# Protections.net
KiCad netlist of a schematic drawn in Altium Designer
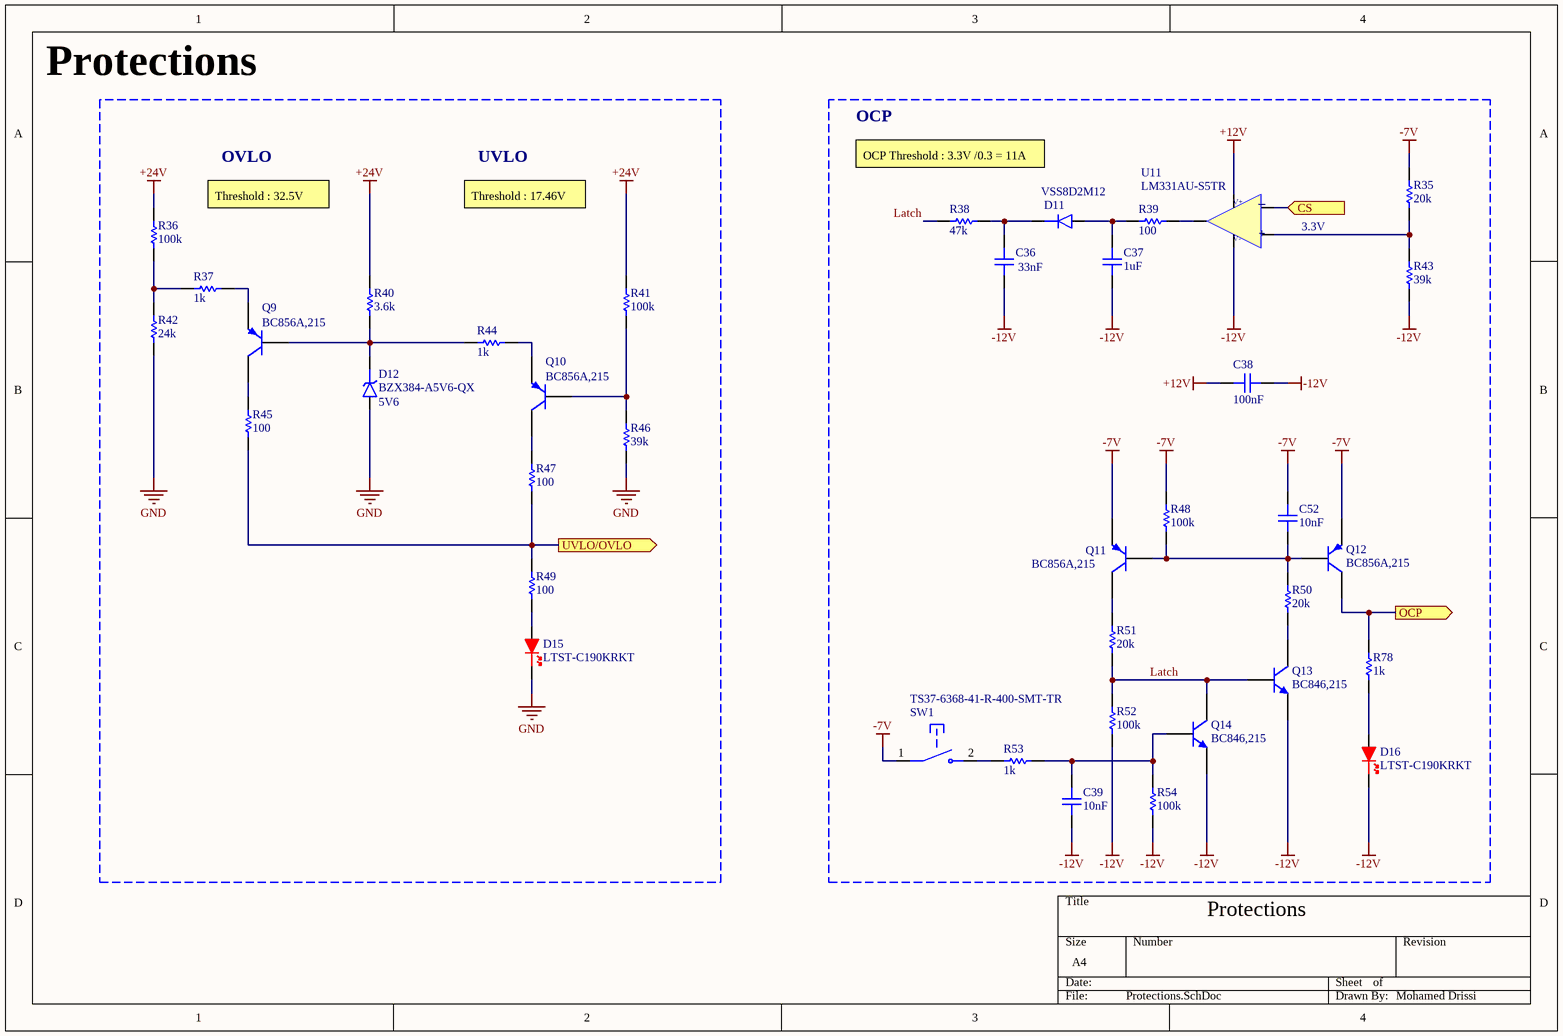
[diagram p0: Protections.SchDoc]

(export (version "E")
  (design (tool "Eeschema 10.0.6"))
  (components
    (comp (ref "C36")
      (value "CC0603KRX7R0BB333")
      (footprint "cap_0603")
      (description "100V 33nF X7R ±10% 0603 Multilayer Ceramic Capacitors MLCC - SMD/SMT ROHS")
      (fields (field (name "MANUFACTURER") "Yageo Group") (field (name "CAPACITANCE") "33nF"))
      (libsource (lib "Inverting buck boost") (part "Yageo CC0603KRX7R0BB333"))
    )
    (comp (ref "C37")
      (value "885382208005")
      (footprint "cap_1206")
      (description "WCAP-CSST 1206 (3216Metric) ceramic capacitor 0.126Lx0.063W 3.20mmx1.60mm X7R ±10% 1muF")
      (fields (field (name "MANUFACTURER") "Wurth Elektronik") (field (name "CAPACITANCE") "1uF"))
      (libsource (lib "Inverting buck boost") (part "Wurth 885382208005"))
    )
    (comp (ref "C38")
      (value "GMC10X7R104K100NT")
      (footprint "cap_0603")
      (description "100V 100nF X7R ±10% 0603 Multilayer Ceramic Capacitors MLCC - SMD/SMT ROHS")
      (fields (field (name "MANUFACTURER") "Cal-Chip Electronics") (field (name "CAPACITANCE") "100nF"))
      (libsource (lib "Inverting buck boost") (part "Cal-chip GMC10X7R104K100NT"))
    )
    (comp (ref "C39")
      (value "C0603C103K4RACTU")
      (footprint "cap_0603")
      (description "Multilayer Ceramic Capacitors MLCC - SMD/SMT 16V 0.01uF X7R 0603 10%")
      (fields
        (field (name "MANUFACTURER") "Yageo Group")
        (field (name "TOLERANCE") "10%")
        (field (name "CAPACITANCE") "10nF")
      )
      (libsource (lib "Inverting buck boost") (part "Yageo C0603C103K4RACTU"))
    )
    (comp (ref "C52")
      (value "C0603C103K4RACTU")
      (footprint "cap_0603")
      (description "Multilayer Ceramic Capacitors MLCC - SMD/SMT 16V 0.01uF X7R 0603 10%")
      (fields
        (field (name "MANUFACTURER") "Yageo Group")
        (field (name "TOLERANCE") "10%")
        (field (name "CAPACITANCE") "10nF")
      )
      (libsource (lib "Inverting buck boost") (part "Yageo C0603C103K4RACTU"))
    )
    (comp (ref "D11")
      (value "VSS8D2M12")
      (footprint "DO-221AD")
      (description "Rectifier Diode, Schottky, 1 Phase, 1 Element, 2A, 120V V(RRM), Silicon, DO-221AD")
      (fields
        (field (name "MANUFACTURER") "Vishay")
        (field (name "MANUFACTURER PART NUMBER") "VSS8D2M12-M3/H")
      )
      (libsource (lib "Inverting buck boost") (part "Vishay VSS8D2M12-M3/H"))
    )
    (comp (ref "D12")
      (value "BZX384-A5V6-QX")
      (footprint "SOD-323")
      (description "Diode Zener 5.6V 300MW SOD323")
      (fields (field (name "MANUFACTURER") "Nexperia") (field (name "ZENER VOLTAGE") "5V6"))
      (libsource (lib "Inverting buck boost") (part "NXP BZX384-A5V6-QX"))
    )
    (comp (ref "D15")
      (value "LTST-C190KRKT")
      (footprint "LED")
      (description "LED red 0603 wavelength 631nm light intensity 18~180mcd Front Mounting")
      (fields (field (name "MANUFACTURER") "Diodes Inc.") (field (name "TOLERANCE") "20%"))
      (libsource (lib "Inverting buck boost") (part "Diodes LTST-C190KRKT"))
    )
    (comp (ref "D16")
      (value "LTST-C190KRKT")
      (footprint "LED")
      (description "LED red 0603 wavelength 631nm light intensity 18~180mcd Front Mounting")
      (fields (field (name "MANUFACTURER") "Diodes Inc.") (field (name "TOLERANCE") "20%"))
      (libsource (lib "Inverting buck boost") (part "Diodes LTST-C190KRKT"))
    )
    (comp (ref "Q9")
      (value "BC856A,215")
      (footprint "sot23")
      (description "BC856 Series 65 V 100 mA SMT PNP General Purpose Transistor - SOT-23")
      (fields (field (name "MANUFACTURER") "Nexperia"))
      (libsource (lib "Inverting buck boost") (part "NXP BC856A,215"))
    )
    (comp (ref "Q10")
      (value "BC856A,215")
      (footprint "sot23")
      (description "BC856 Series 65 V 100 mA SMT PNP General Purpose Transistor - SOT-23")
      (fields (field (name "MANUFACTURER") "Nexperia"))
      (libsource (lib "Inverting buck boost") (part "NXP BC856A,215"))
    )
    (comp (ref "Q11")
      (value "BC856A,215")
      (footprint "sot23")
      (description "BC856 Series 65 V 100 mA SMT PNP General Purpose Transistor - SOT-23")
      (fields (field (name "MANUFACTURER") "Nexperia"))
      (libsource (lib "Inverting buck boost") (part "NXP BC856A,215"))
    )
    (comp (ref "Q12")
      (value "BC856A,215")
      (footprint "sot23")
      (description "BC856 Series 65 V 100 mA SMT PNP General Purpose Transistor - SOT-23")
      (fields (field (name "MANUFACTURER") "Nexperia"))
      (libsource (lib "Inverting buck boost") (part "NXP BC856A,215"))
    )
    (comp (ref "Q13")
      (value "BC846,215")
      (footprint "sot23")
      (description "BC846 Series 65 V 100 mA SMT NPN General Purpose Transistor - SOT-23")
      (fields (field (name "MANUFACTURER") "Nexperia"))
      (libsource (lib "Inverting buck boost") (part "NXP BC846,215"))
    )
    (comp (ref "Q14")
      (value "BC846,215")
      (footprint "sot23")
      (description "BC846 Series 65 V 100 mA SMT NPN General Purpose Transistor - SOT-23")
      (fields (field (name "MANUFACTURER") "Nexperia"))
      (libsource (lib "Inverting buck boost") (part "NXP BC846,215"))
    )
    (comp (ref "R35")
      (value "20k")
      (footprint "res_0603")
      (description "63mW Thin Film Resistor ±50ppm/℃ ±1% 20kΩ 0603 Chip Resistor - Surface Mount ROHS")
      (fields
        (field (name "MANUFACTURER") "TE Connectivity")
        (field (name "MANUFACTURER PART NUMBER") "8-1879337-8")
      )
      (libsource (lib "Inverting buck boost") (part "TE 8-1879337-8"))
    )
    (comp (ref "R36")
      (value "CRCW0603100KFKEA")
      (footprint "res_0603")
      (description "Res Thick Film 0603 100K Ohm 1% 1/3W ±100ppm/°C Molded SMD SMD Paper T/R")
      (fields
        (field (name "MANUFACTURER") "Vishay")
        (field (name "MANUFACTURER PART NUMBER") "CRCW0603100KFKEAHP")
        (field (name "RESISTANCE") "100k")
      )
      (libsource (lib "Inverting buck boost") (part "Vishay CRCW0603100KFKEAHP"))
    )
    (comp (ref "R37")
      (value "RC0603FR-071KL")
      (footprint "res_0603")
      (description "Res Thick Film 0603 1K Ohm 1% 0.1W(1/10W) ±100ppm/°C Pad SMD T/R / RES SMD 1K OHM 1% 1/10W 0603")
      (fields
        (field (name "MANUFACTURER") "Yageo Group")
        (field (name "TOLERANCE") "1%")
        (field (name "RESISTANCE") "1k")
      )
      (libsource (lib "Inverting buck boost") (part "Yageo RC0603FR-071KL"))
    )
    (comp (ref "R38")
      (value "RC0603FR-0747KL")
      (footprint "res_0603")
      (description "Res Thick Film 0603 47K Ohm 1% 1/10W ±100ppm/°C Molded SMD Paper T/R")
      (fields
        (field (name "MANUFACTURER") "Yageo Group")
        (field (name "TOLERANCE") "1%")
        (field (name "RESISTANCE") "47k")
      )
      (libsource (lib "Inverting buck boost") (part "Yageo RC0603FR-0747KL"))
    )
    (comp (ref "R39")
      (value "RC0603FR-07100RL")
      (footprint "res_0603")
      (description "Yageo RC0603FR-07100RL 0603 SMD Resistor 100 Ohm thin film chip resistor")
      (fields
        (field (name "MANUFACTURER") "Yageo Group")
        (field (name "TOLERANCE") "1%")
        (field (name "RESISTANCE") "100")
      )
      (libsource (lib "Inverting buck boost") (part "Yageo RC0603FR-07100RL"))
    )
    (comp (ref "R40")
      (value "RC0603FR-073K6L")
      (footprint "res_0603")
      (description "100mW Thick Film Resistors 75V ±100ppm/℃ ±1% 3.6kΩ 0603 Chip Resistor - Surface Mount ROHS")
      (fields
        (field (name "MANUFACTURER") "Yageo Group")
        (field (name "TOLERANCE") "1%")
        (field (name "RESISTANCE") "3.6k")
      )
      (libsource (lib "Inverting buck boost") (part "YageoRC0603FR-073K6L"))
    )
    (comp (ref "R41")
      (value "CRCW0603100KFKEA")
      (footprint "res_0603")
      (description "Res Thick Film 0603 100K Ohm 1% 1/3W ±100ppm/°C Molded SMD SMD Paper T/R")
      (fields
        (field (name "MANUFACTURER") "Vishay")
        (field (name "MANUFACTURER PART NUMBER") "CRCW0603100KFKEAHP")
        (field (name "RESISTANCE") "100k")
      )
      (libsource (lib "Inverting buck boost") (part "Vishay CRCW0603100KFKEAHP"))
    )
    (comp (ref "R42")
      (value "RC0603FR-0724KL")
      (footprint "res_0603")
      (description "100mW Thick Film Resistors 75V ±100ppm/℃ ±1% 24kΩ 0603 Chip Resistor - Surface Mount ROHS")
      (fields
        (field (name "MANUFACTURER") "Yageo Group")
        (field (name "TOLERANCE") "1%")
        (field (name "RESISTANCE") "24k")
      )
      (libsource (lib "Inverting buck boost") (part "Yageo RC0603FR-0724KL"))
    )
    (comp (ref "R43")
      (value "39k")
      (footprint "res_0603")
      (description "Res Thin Film 0603 39K Ohm 1% 1/10W ±50ppm/°C Molded SMD SMD Paper T/R")
      (fields
        (field (name "MANUFACTURER") "Vishay")
        (field (name "MANUFACTURER PART NUMBER") "MCT06030C3902FP500")
      )
      (libsource (lib "Inverting buck boost") (part "Vishay MCT06030C3902FP500"))
    )
    (comp (ref "R44")
      (value "RC0603FR-071KL")
      (footprint "res_0603")
      (description "Res Thick Film 0603 1K Ohm 1% 0.1W(1/10W) ±100ppm/°C Pad SMD T/R / RES SMD 1K OHM 1% 1/10W 0603")
      (fields
        (field (name "MANUFACTURER") "Yageo Group")
        (field (name "TOLERANCE") "1%")
        (field (name "RESISTANCE") "1k")
      )
      (libsource (lib "Inverting buck boost") (part "Yageo RC0603FR-071KL"))
    )
    (comp (ref "R45")
      (value "RC0603FR-07100RL")
      (footprint "res_0603")
      (description "Yageo RC0603FR-07100RL 0603 SMD Resistor 100 Ohm thin film chip resistor")
      (fields
        (field (name "MANUFACTURER") "Yageo Group")
        (field (name "TOLERANCE") "1%")
        (field (name "RESISTANCE") "100")
      )
      (libsource (lib "Inverting buck boost") (part "Yageo RC0603FR-07100RL"))
    )
    (comp (ref "R46")
      (value "RC0603FR-0739KL")
      (footprint "res_0603")
      (description "100mW Thick Film Resistors 75V ±100ppm/℃ ±1% 39kΩ 0603 Chip Resistor - Surface Mount ROHS")
      (fields
        (field (name "MANUFACTURER") "Yageo Group")
        (field (name "TOLERANCE") "1%")
        (field (name "RESISTANCE") "39k")
      )
      (libsource (lib "Inverting buck boost") (part "Yageo RC0603FR-0739KL"))
    )
    (comp (ref "R47")
      (value "RC0603FR-07100RL")
      (footprint "res_0603")
      (description "Yageo RC0603FR-07100RL 0603 SMD Resistor 100 Ohm thin film chip resistor")
      (fields
        (field (name "MANUFACTURER") "Yageo Group")
        (field (name "TOLERANCE") "1%")
        (field (name "RESISTANCE") "100")
      )
      (libsource (lib "Inverting buck boost") (part "Yageo RC0603FR-07100RL"))
    )
    (comp (ref "R48")
      (value "CRCW0603100KFKEA")
      (footprint "res_0603")
      (description "Res Thick Film 0603 100K Ohm 1% 1/3W ±100ppm/°C Molded SMD SMD Paper T/R")
      (fields
        (field (name "MANUFACTURER") "Vishay")
        (field (name "MANUFACTURER PART NUMBER") "CRCW0603100KFKEAHP")
        (field (name "RESISTANCE") "100k")
      )
      (libsource (lib "Inverting buck boost") (part "Vishay CRCW0603100KFKEAHP"))
    )
    (comp (ref "R49")
      (value "RC0603FR-07100RL")
      (footprint "res_0603")
      (description "Yageo RC0603FR-07100RL 0603 SMD Resistor 100 Ohm thin film chip resistor")
      (fields
        (field (name "MANUFACTURER") "Yageo Group")
        (field (name "TOLERANCE") "1%")
        (field (name "RESISTANCE") "100")
      )
      (libsource (lib "Inverting buck boost") (part "Yageo RC0603FR-07100RL"))
    )
    (comp (ref "R50")
      (value "20k")
      (footprint "res_0603")
      (description "63mW Thin Film Resistor ±50ppm/℃ ±1% 20kΩ 0603 Chip Resistor - Surface Mount ROHS")
      (fields
        (field (name "MANUFACTURER") "TE Connectivity")
        (field (name "MANUFACTURER PART NUMBER") "8-1879337-8")
      )
      (libsource (lib "Inverting buck boost") (part "TE 8-1879337-8"))
    )
    (comp (ref "R51")
      (value "20k")
      (footprint "res_0603")
      (description "63mW Thin Film Resistor ±50ppm/℃ ±1% 20kΩ 0603 Chip Resistor - Surface Mount ROHS")
      (fields
        (field (name "MANUFACTURER") "TE Connectivity")
        (field (name "MANUFACTURER PART NUMBER") "8-1879337-8")
      )
      (libsource (lib "Inverting buck boost") (part "TE 8-1879337-8"))
    )
    (comp (ref "R52")
      (value "CRCW0603100KFKEA")
      (footprint "res_0603")
      (description "Res Thick Film 0603 100K Ohm 1% 1/3W ±100ppm/°C Molded SMD SMD Paper T/R")
      (fields
        (field (name "MANUFACTURER") "Vishay")
        (field (name "MANUFACTURER PART NUMBER") "CRCW0603100KFKEAHP")
        (field (name "RESISTANCE") "100k")
      )
      (libsource (lib "Inverting buck boost") (part "Vishay CRCW0603100KFKEAHP"))
    )
    (comp (ref "R53")
      (value "RC0603FR-071KL")
      (footprint "res_0603")
      (description "Res Thick Film 0603 1K Ohm 1% 0.1W(1/10W) ±100ppm/°C Pad SMD T/R / RES SMD 1K OHM 1% 1/10W 0603")
      (fields
        (field (name "MANUFACTURER") "Yageo Group")
        (field (name "TOLERANCE") "1%")
        (field (name "RESISTANCE") "1k")
      )
      (libsource (lib "Inverting buck boost") (part "Yageo RC0603FR-071KL"))
    )
    (comp (ref "R54")
      (value "CRCW0603100KFKEA")
      (footprint "res_0603")
      (description "Res Thick Film 0603 100K Ohm 1% 1/3W ±100ppm/°C Molded SMD SMD Paper T/R")
      (fields
        (field (name "MANUFACTURER") "Vishay")
        (field (name "MANUFACTURER PART NUMBER") "CRCW0603100KFKEAHP")
        (field (name "RESISTANCE") "100k")
      )
      (libsource (lib "Inverting buck boost") (part "Vishay CRCW0603100KFKEAHP"))
    )
    (comp (ref "R78")
      (value "RC0603FR-071KL")
      (footprint "res_0603")
      (description "Res Thick Film 0603 1K Ohm 1% 0.1W(1/10W) ±100ppm/°C Pad SMD T/R / RES SMD 1K OHM 1% 1/10W 0603")
      (fields
        (field (name "MANUFACTURER") "Yageo Group")
        (field (name "TOLERANCE") "1%")
        (field (name "RESISTANCE") "1k")
      )
      (libsource (lib "Inverting buck boost") (part "Yageo RC0603FR-071KL"))
    )
    (comp (ref "SW1")
      (value "TS37-6368-41-R-400-SMT-TR")
      (footprint "TS37-6368-41-R-400-SMT-TR")
      (description "6.3 x 6.8 mm, 4.1 mm Actuator Height Off PCB, 400 gf, Red, Surface Mount, SPST, Tactile Switch")
      (fields (field (name "MANUFACTURER") "Same Sky"))
      (libsource (lib "Inverting buck boost") (part "Same Sky TS37-6368-41-R-400-SMT-TR"))
    )
    (comp (ref "U11")
      (value "LM331AU-S5TR")
      (footprint "5-Lead SOT-23")
      (description "150μA 500ns Open Collector, Rail to Rail 20mA 1 2.5V ±18V, 36V 6mV@ 5V 4nA@ 5V SOT-23-5 , 2.9mm")
      (fields (field (name "MANUFACTURER") "3Peak"))
      (libsource (lib "Inverting buck boost") (part "3Peak LM331AU-S5TR"))
    )
  )
  (nets
    (net (code "1") (name "+12V") (class "Default")
      (node (ref "C38") (pin "2") (pinfunction "2_2") (pintype "passive"))
      (node (ref "U11") (pin "5") (pinfunction "V+_5") (pintype "passive"))
    )
    (net (code "2") (name "+24V") (class "Default")
      (node (ref "R36") (pin "2") (pinfunction "2_2") (pintype "passive"))
      (node (ref "R40") (pin "2") (pinfunction "2_2") (pintype "passive"))
      (node (ref "R41") (pin "2") (pinfunction "2_2") (pintype "passive"))
    )
    (net (code "3") (name "-7V") (class "Default")
      (node (ref "C52") (pin "2") (pinfunction "2_2") (pintype "passive"))
      (node (ref "Q11") (pin "2") (pinfunction "E_2") (pintype "passive"))
      (node (ref "Q12") (pin "2") (pinfunction "E_2") (pintype "passive"))
      (node (ref "R35") (pin "2") (pinfunction "2_2") (pintype "passive"))
      (node (ref "R48") (pin "2") (pinfunction "2_2") (pintype "passive"))
      (node (ref "SW1") (pin "1") (pinfunction "1_1") (pintype "passive"))
    )
    (net (code "4") (name "-12V") (class "Default")
      (node (ref "C36") (pin "1") (pinfunction "1_1") (pintype "passive"))
      (node (ref "C37") (pin "1") (pinfunction "1_1") (pintype "passive"))
      (node (ref "C38") (pin "1") (pinfunction "1_1") (pintype "passive"))
      (node (ref "C39") (pin "1") (pinfunction "1_1") (pintype "passive"))
      (node (ref "D16") (pin "K") (pinfunction "K_K") (pintype "passive"))
      (node (ref "Q13") (pin "2") (pinfunction "E_2") (pintype "passive"))
      (node (ref "Q14") (pin "2") (pinfunction "E_2") (pintype "passive"))
      (node (ref "R43") (pin "1") (pinfunction "1_1") (pintype "passive"))
      (node (ref "R52") (pin "1") (pinfunction "1_1") (pintype "passive"))
      (node (ref "R54") (pin "1") (pinfunction "1_1") (pintype "passive"))
      (node (ref "U11") (pin "2") (pinfunction "V-_2") (pintype "passive"))
    )
    (net (code "5") (name "/CS") (class "Default")
      (node (ref "U11") (pin "3") (pinfunction "IN+_3") (pintype "passive"))
    )
    (net (code "6") (name "/Latch") (class "Default")
      (node (ref "Q13") (pin "1") (pinfunction "B_1") (pintype "passive"))
      (node (ref "Q14") (pin "3") (pinfunction "C_3") (pintype "passive"))
      (node (ref "R38") (pin "1") (pinfunction "1_1") (pintype "passive"))
      (node (ref "R51") (pin "1") (pinfunction "1_1") (pintype "passive"))
      (node (ref "R52") (pin "2") (pinfunction "2_2") (pintype "passive"))
    )
    (net (code "7") (name "/OCP") (class "Default")
      (node (ref "Q12") (pin "3") (pinfunction "C_3") (pintype "passive"))
      (node (ref "R78") (pin "2") (pinfunction "2_2") (pintype "passive"))
    )
    (net (code "8") (name "/UVLO{slash}OVLO") (class "Default")
      (node (ref "R45") (pin "1") (pinfunction "1_1") (pintype "passive"))
      (node (ref "R47") (pin "1") (pinfunction "1_1") (pintype "passive"))
      (node (ref "R49") (pin "2") (pinfunction "2_2") (pintype "passive"))
    )
    (net (code "9") (name "GND") (class "Default")
      (node (ref "D12") (pin "A") (pinfunction "A_A") (pintype "passive"))
      (node (ref "D15") (pin "K") (pinfunction "K_K") (pintype "passive"))
      (node (ref "R42") (pin "1") (pinfunction "1_1") (pintype "passive"))
      (node (ref "R46") (pin "1") (pinfunction "1_1") (pintype "passive"))
    )
    (net (code "10") (name "Net-(C36-Pad2)") (class "Default")
      (node (ref "C36") (pin "2") (pinfunction "2_2") (pintype "passive"))
      (node (ref "D11") (pin "C") (pinfunction "C_C") (pintype "passive"))
      (node (ref "R38") (pin "2") (pinfunction "2_2") (pintype "passive"))
    )
    (net (code "11") (name "Net-(C37-Pad2)") (class "Default")
      (node (ref "C37") (pin "2") (pinfunction "2_2") (pintype "passive"))
      (node (ref "D11") (pin "A") (pinfunction "A_A") (pintype "passive"))
      (node (ref "R39") (pin "1") (pinfunction "1_1") (pintype "passive"))
    )
    (net (code "12") (name "Net-(D15-PadA)") (class "Default")
      (node (ref "D15") (pin "A") (pinfunction "A_A") (pintype "passive"))
      (node (ref "R49") (pin "1") (pinfunction "1_1") (pintype "passive"))
    )
    (net (code "13") (name "Net-(D16-PadA)") (class "Default")
      (node (ref "D16") (pin "A") (pinfunction "A_A") (pintype "passive"))
      (node (ref "R78") (pin "1") (pinfunction "1_1") (pintype "passive"))
    )
    (net (code "14") (name "Net-(Q9-B)") (class "Default")
      (node (ref "D12") (pin "K") (pinfunction "K_K") (pintype "passive"))
      (node (ref "Q9") (pin "1") (pinfunction "B_1") (pintype "passive"))
      (node (ref "R40") (pin "1") (pinfunction "1_1") (pintype "passive"))
      (node (ref "R44") (pin "1") (pinfunction "1_1") (pintype "passive"))
    )
    (net (code "15") (name "Net-(Q9-C)") (class "Default")
      (node (ref "Q9") (pin "3") (pinfunction "C_3") (pintype "passive"))
      (node (ref "R45") (pin "2") (pinfunction "2_2") (pintype "passive"))
    )
    (net (code "16") (name "Net-(Q9-E)") (class "Default")
      (node (ref "Q9") (pin "2") (pinfunction "E_2") (pintype "passive"))
      (node (ref "R37") (pin "2") (pinfunction "2_2") (pintype "passive"))
    )
    (net (code "17") (name "Net-(Q10-B)") (class "Default")
      (node (ref "Q10") (pin "1") (pinfunction "B_1") (pintype "passive"))
      (node (ref "R41") (pin "1") (pinfunction "1_1") (pintype "passive"))
      (node (ref "R46") (pin "2") (pinfunction "2_2") (pintype "passive"))
    )
    (net (code "18") (name "Net-(Q10-C)") (class "Default")
      (node (ref "Q10") (pin "3") (pinfunction "C_3") (pintype "passive"))
      (node (ref "R47") (pin "2") (pinfunction "2_2") (pintype "passive"))
    )
    (net (code "19") (name "Net-(Q10-E)") (class "Default")
      (node (ref "Q10") (pin "2") (pinfunction "E_2") (pintype "passive"))
      (node (ref "R44") (pin "2") (pinfunction "2_2") (pintype "passive"))
    )
    (net (code "20") (name "Net-(Q11-B)") (class "Default")
      (node (ref "C52") (pin "1") (pinfunction "1_1") (pintype "passive"))
      (node (ref "Q11") (pin "1") (pinfunction "B_1") (pintype "passive"))
      (node (ref "Q12") (pin "1") (pinfunction "B_1") (pintype "passive"))
      (node (ref "R48") (pin "1") (pinfunction "1_1") (pintype "passive"))
      (node (ref "R50") (pin "2") (pinfunction "2_2") (pintype "passive"))
    )
    (net (code "21") (name "Net-(Q11-C)") (class "Default")
      (node (ref "Q11") (pin "3") (pinfunction "C_3") (pintype "passive"))
      (node (ref "R51") (pin "2") (pinfunction "2_2") (pintype "passive"))
    )
    (net (code "22") (name "Net-(Q13-C)") (class "Default")
      (node (ref "Q13") (pin "3") (pinfunction "C_3") (pintype "passive"))
      (node (ref "R50") (pin "1") (pinfunction "1_1") (pintype "passive"))
    )
    (net (code "23") (name "Net-(Q14-B)") (class "Default")
      (node (ref "C39") (pin "2") (pinfunction "2_2") (pintype "passive"))
      (node (ref "Q14") (pin "1") (pinfunction "B_1") (pintype "passive"))
      (node (ref "R53") (pin "2") (pinfunction "2_2") (pintype "passive"))
      (node (ref "R54") (pin "2") (pinfunction "2_2") (pintype "passive"))
    )
    (net (code "24") (name "Net-(R36-Pad1)") (class "Default")
      (node (ref "R36") (pin "1") (pinfunction "1_1") (pintype "passive"))
      (node (ref "R37") (pin "1") (pinfunction "1_1") (pintype "passive"))
      (node (ref "R42") (pin "2") (pinfunction "2_2") (pintype "passive"))
    )
    (net (code "25") (name "Net-(R53-Pad1)") (class "Default")
      (node (ref "R53") (pin "1") (pinfunction "1_1") (pintype "passive"))
      (node (ref "SW1") (pin "2") (pinfunction "2_2") (pintype "passive"))
    )
    (net (code "26") (name "Net-(U11-IN-)") (class "Default")
      (node (ref "R35") (pin "1") (pinfunction "1_1") (pintype "passive"))
      (node (ref "R43") (pin "2") (pinfunction "2_2") (pintype "passive"))
      (node (ref "U11") (pin "1") (pinfunction "IN-_1") (pintype "passive"))
    )
    (net (code "27") (name "Net-(U11-OUT)") (class "Default")
      (node (ref "R39") (pin "2") (pinfunction "2_2") (pintype "passive"))
      (node (ref "U11") (pin "4") (pinfunction "OUT_4") (pintype "passive"))
    )
  )
)
